# SCH_myFirstPcbBoard_2025-02-05.net
KiCad netlist of a schematic drawn in EasyEDA
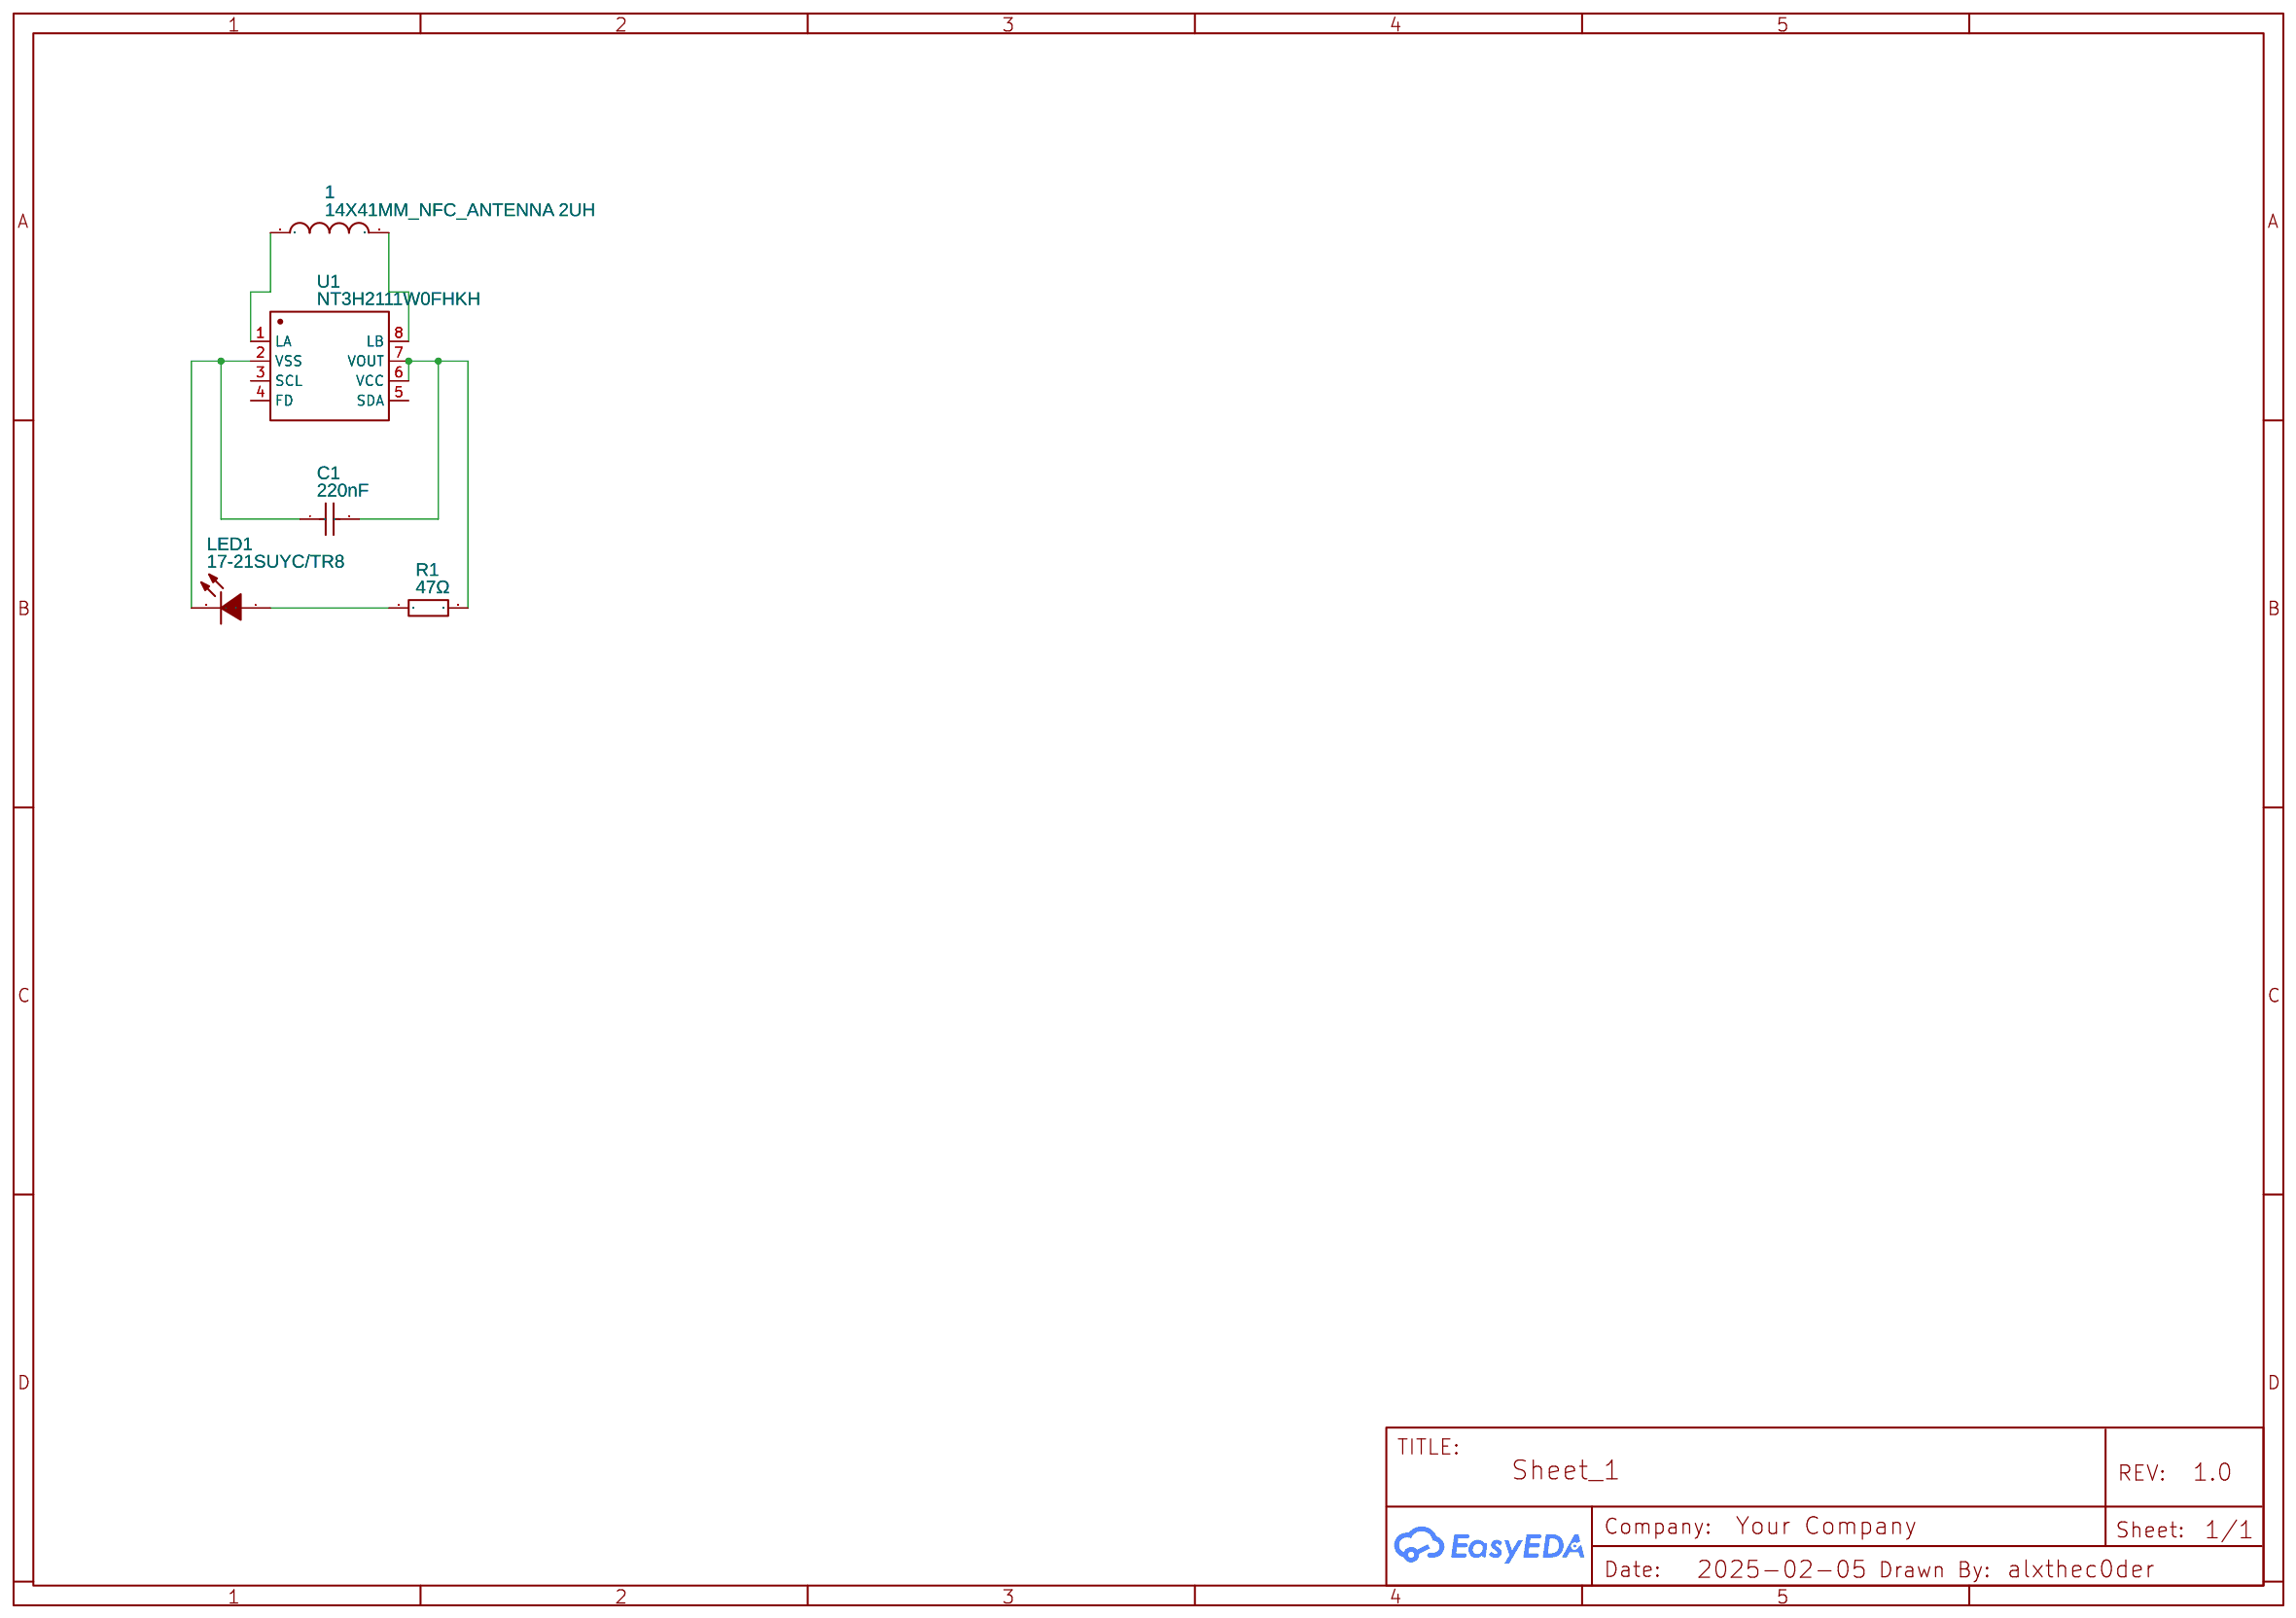
[diagram p0: schematic sheet]

(export (version "E")
  (design (tool "Eeschema 10.0.6"))
  (components
    (comp (ref "1") (value "14X41MM_NFC_ANTENNA 2UH") (libsource (lib "") (part "14X41MM_NFC_ANTENNA 2UH")))
    (comp (ref "C1")
      (value "220nF")
      (fields
        (field (name "Manufacturer Part") "CL10B224KA8NNNC")
        (field (name "Manufacturer") "SAMSUNG(三星)")
      )
      (libsource (lib "") (part "CL10B224KA8NNNC"))
    )
    (comp (ref "LED1")
      (value "17-21SUYC/TR8")
      (fields (field (name "Manufacturer Part") "KT-0805黄灯") (field (name "Manufacturer") "KENTO"))
      (libsource (lib "") (part "17-21SUYC/TR8"))
    )
    (comp (ref "R1")
      (value "47Ω")
      (fields
        (field (name "Manufacturer Part") "0603WAF470JT5E")
        (field (name "Manufacturer") "UNI-ROYAL(厚声)")
      )
      (libsource (lib "") (part "0603WAF470JT5E"))
    )
    (comp (ref "U1")
      (value "NT3H2111W0FHKH")
      (fields (field (name "Manufacturer") "NXP(恩智浦)"))
      (libsource (lib "") (part "NT3H2111W0FHKH"))
    )
  )
  (nets
    (net (code "1") (name "Net-(LED1-+)") (class "Default")
      (node (ref "LED1") (pin "1") (pinfunction "+_1") (pintype "unspecified"))
      (node (ref "R1") (pin "1") (pinfunction "1_1") (pintype "input"))
    )
    (net (code "2") (name "Net-(LED1--)") (class "Default")
      (node (ref "C1") (pin "1") (pinfunction "1_1") (pintype "input"))
      (node (ref "LED1") (pin "2") (pinfunction "-_2") (pintype "unspecified"))
      (node (ref "U1") (pin "2") (pinfunction "VSS_2") (pintype "unspecified"))
    )
    (net (code "3") (name "Net-(U1-LA)") (class "Default")
      (node (ref "1") (pin "P$1") (pinfunction "P$1_P$1") (pintype "bidirectional"))
      (node (ref "U1") (pin "1") (pinfunction "LA_1") (pintype "unspecified"))
    )
    (net (code "4") (name "Net-(U1-LB)") (class "Default")
      (node (ref "1") (pin "P$2") (pinfunction "P$2_P$2") (pintype "bidirectional"))
      (node (ref "U1") (pin "8") (pinfunction "LB_8") (pintype "unspecified"))
    )
    (net (code "5") (name "Net-(U1-VCC)") (class "Default")
      (node (ref "C1") (pin "2") (pinfunction "2_2") (pintype "input"))
      (node (ref "R1") (pin "2") (pinfunction "2_2") (pintype "input"))
      (node (ref "U1") (pin "6") (pinfunction "VCC_6") (pintype "unspecified"))
      (node (ref "U1") (pin "7") (pinfunction "VOUT_7") (pintype "unspecified"))
    )
    (net (code "6") (name "unconnected-(U1-FD-Pad4)") (class "Default")
      (node (ref "U1") (pin "4") (pinfunction "FD_4") (pintype "unspecified"))
    )
    (net (code "7") (name "unconnected-(U1-SCL-Pad3)") (class "Default")
      (node (ref "U1") (pin "3") (pinfunction "SCL_3") (pintype "unspecified"))
    )
    (net (code "8") (name "unconnected-(U1-SDA-Pad5)") (class "Default")
      (node (ref "U1") (pin "5") (pinfunction "SDA_5") (pintype "unspecified"))
    )
  )
)
